# Motor-Driver-Breakout.net
KiCad netlist of a schematic drawn in EAGLE
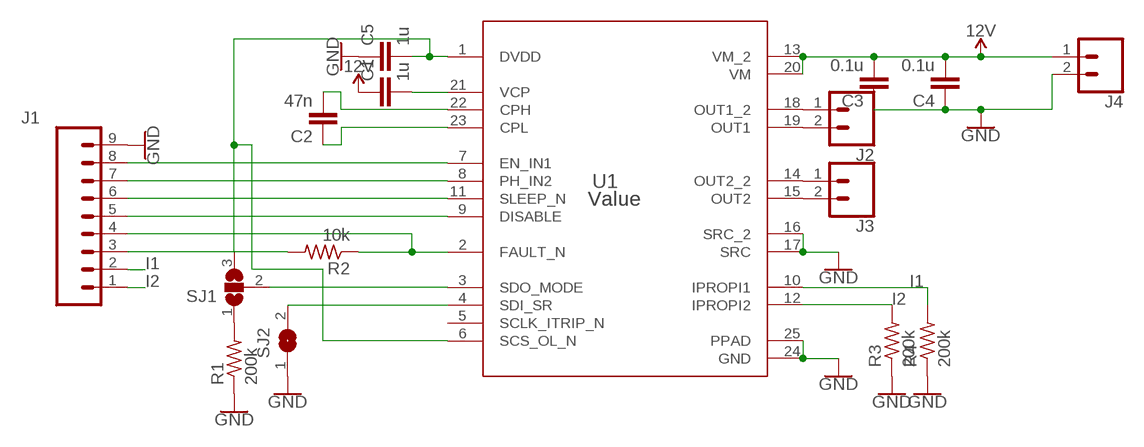
[diagram p0: schematic, sheet 1]

(export (version "E")
  (design (tool "Eeschema 10.0.6"))
  (components
    (comp (ref "C1")
      (value "1u")
      (footprint "eagle-import:0603-C")
      (libsource (lib "eagle-import") (part "C0603"))
    )
    (comp (ref "C2")
      (value "47n")
      (footprint "eagle-import:0603-C")
      (libsource (lib "eagle-import") (part "C0603"))
    )
    (comp (ref "C3")
      (value "0.1u")
      (footprint "eagle-import:0603-C")
      (libsource (lib "eagle-import") (part "C0603"))
    )
    (comp (ref "C4")
      (value "0.1u")
      (footprint "eagle-import:0603-C")
      (libsource (lib "eagle-import") (part "C0603"))
    )
    (comp (ref "C5")
      (value "1u")
      (footprint "eagle-import:0603-C")
      (libsource (lib "eagle-import") (part "C0603"))
    )
    (comp (ref "J1")
      (value "CONN_09")
      (footprint "eagle-import:1X09")
      (libsource (lib "eagle-import") (part "CONN_09"))
    )
    (comp (ref "J2")
      (value "CONN_02")
      (footprint "eagle-import:1X02")
      (libsource (lib "eagle-import") (part "CONN_02"))
    )
    (comp (ref "J3")
      (value "CONN_02")
      (footprint "eagle-import:1X02")
      (libsource (lib "eagle-import") (part "CONN_02"))
    )
    (comp (ref "J4")
      (value "CONN_02")
      (footprint "eagle-import:1X02")
      (libsource (lib "eagle-import") (part "CONN_02"))
    )
    (comp (ref "R1")
      (value "200k")
      (footprint "eagle-import:0603-R")
      (libsource (lib "eagle-import") (part "R0603"))
    )
    (comp (ref "R2")
      (value "10k")
      (footprint "eagle-import:0603-R")
      (libsource (lib "eagle-import") (part "R0603"))
    )
    (comp (ref "R3")
      (value "200k")
      (footprint "eagle-import:0603-R")
      (libsource (lib "eagle-import") (part "R0603"))
    )
    (comp (ref "R4")
      (value "200k")
      (footprint "eagle-import:0603-R")
      (libsource (lib "eagle-import") (part "R0603"))
    )
    (comp (ref "SJ1")
      (value "SJ2W")
      (footprint "eagle-import:SJ_2")
      (libsource (lib "eagle-import") (part "SJ2W"))
    )
    (comp (ref "SJ2") (value "SJ") (footprint "eagle-import:SJ") (libsource (lib "eagle-import") (part "SJ")))
    (comp (ref "U1")
      (value "Value")
      (footprint "eagle-import:PWP0024J_N")
      (fields (field (name "MANUFACTURER") "Texas Instruments") (field (name "PARTNUMBER") "DRV8873SPWPRQ1"))
      (libsource (lib "eagle-import") (part "DRV8873HPWPRQ1"))
    )
  )
  (nets
    (net (code "1") (name "/I1") (class "Default")
      (node (ref "J1") (pin "2") (pinfunction "2_2") (pintype "passive"))
      (node (ref "R4") (pin "2") (pinfunction "2_2") (pintype "passive"))
      (node (ref "U1") (pin "10") (pinfunction "IPROPI1_10") (pintype "passive"))
    )
    (net (code "2") (name "/I2") (class "Default")
      (node (ref "J1") (pin "1") (pinfunction "1_1") (pintype "passive"))
      (node (ref "R3") (pin "2") (pinfunction "2_2") (pintype "passive"))
      (node (ref "U1") (pin "12") (pinfunction "IPROPI2_12") (pintype "passive"))
    )
    (net (code "3") (name "12V") (class "Default")
      (node (ref "C1") (pin "1") (pinfunction "1_1") (pintype "passive"))
      (node (ref "C3") (pin "2") (pinfunction "2_2") (pintype "passive"))
      (node (ref "C4") (pin "2") (pinfunction "2_2") (pintype "passive"))
      (node (ref "J4") (pin "1") (pinfunction "1_1") (pintype "passive"))
      (node (ref "U1") (pin "13") (pinfunction "VM_2_13") (pintype "power_in"))
      (node (ref "U1") (pin "20") (pinfunction "VM_20") (pintype "power_in"))
    )
    (net (code "4") (name "GND") (class "Default")
      (node (ref "C3") (pin "1") (pinfunction "1_1") (pintype "passive"))
      (node (ref "C4") (pin "1") (pinfunction "1_1") (pintype "passive"))
      (node (ref "C5") (pin "1") (pinfunction "1_1") (pintype "passive"))
      (node (ref "J1") (pin "9") (pinfunction "9_9") (pintype "passive"))
      (node (ref "J4") (pin "2") (pinfunction "2_2") (pintype "passive"))
      (node (ref "R1") (pin "1") (pinfunction "1_1") (pintype "passive"))
      (node (ref "R3") (pin "1") (pinfunction "1_1") (pintype "passive"))
      (node (ref "R4") (pin "1") (pinfunction "1_1") (pintype "passive"))
      (node (ref "SJ2") (pin "1") (pinfunction "1_1") (pintype "passive"))
      (node (ref "U1") (pin "16") (pinfunction "SRC_2_16") (pintype "passive"))
      (node (ref "U1") (pin "17") (pinfunction "SRC_17") (pintype "passive"))
      (node (ref "U1") (pin "24") (pinfunction "GND_24") (pintype "power_in"))
      (node (ref "U1") (pin "25") (pinfunction "PPAD_25") (pintype "power_in"))
    )
    (net (code "5") (name "Net-(J1-Pad3)") (class "Default")
      (node (ref "J1") (pin "3") (pinfunction "3_3") (pintype "passive"))
      (node (ref "R2") (pin "2") (pinfunction "2_2") (pintype "passive"))
    )
    (net (code "6") (name "Net-(R1-Pad2)") (class "Default")
      (node (ref "R1") (pin "2") (pinfunction "2_2") (pintype "passive"))
      (node (ref "SJ1") (pin "1") (pinfunction "1_1") (pintype "passive"))
    )
    (net (code "7") (name "Net-(U1-CPH)") (class "Default")
      (node (ref "C2") (pin "2") (pinfunction "2_2") (pintype "passive"))
      (node (ref "U1") (pin "22") (pinfunction "CPH_22") (pintype "power_in"))
    )
    (net (code "8") (name "Net-(U1-CPL)") (class "Default")
      (node (ref "C2") (pin "1") (pinfunction "1_1") (pintype "passive"))
      (node (ref "U1") (pin "23") (pinfunction "CPL_23") (pintype "power_in"))
    )
    (net (code "9") (name "Net-(U1-DISABLE)") (class "Default")
      (node (ref "J1") (pin "5") (pinfunction "5_5") (pintype "passive"))
      (node (ref "U1") (pin "9") (pinfunction "DISABLE_9") (pintype "input"))
    )
    (net (code "10") (name "Net-(U1-DVDD)") (class "Default")
      (node (ref "C5") (pin "2") (pinfunction "2_2") (pintype "passive"))
      (node (ref "SJ1") (pin "3") (pinfunction "3_3") (pintype "passive"))
      (node (ref "U1") (pin "1") (pinfunction "DVDD_1") (pintype "power_in"))
      (node (ref "U1") (pin "6") (pinfunction "SCS_OL_N_6") (pintype "input"))
    )
    (net (code "11") (name "Net-(U1-EN_IN1)") (class "Default")
      (node (ref "J1") (pin "8") (pinfunction "8_8") (pintype "passive"))
      (node (ref "U1") (pin "7") (pinfunction "EN_IN1_7") (pintype "input"))
    )
    (net (code "12") (name "Net-(U1-FAULT_N)") (class "Default")
      (node (ref "J1") (pin "4") (pinfunction "4_4") (pintype "passive"))
      (node (ref "R2") (pin "1") (pinfunction "1_1") (pintype "passive"))
      (node (ref "U1") (pin "2") (pinfunction "FAULT_N_2") (pintype "open_collector"))
    )
    (net (code "13") (name "Net-(U1-OUT1)") (class "Default")
      (node (ref "J2") (pin "2") (pinfunction "2_2") (pintype "passive"))
      (node (ref "U1") (pin "19") (pinfunction "OUT1_19") (pintype "output"))
    )
    (net (code "14") (name "Net-(U1-OUT1_2)") (class "Default")
      (node (ref "J2") (pin "1") (pinfunction "1_1") (pintype "passive"))
      (node (ref "U1") (pin "18") (pinfunction "OUT1_2_18") (pintype "output"))
    )
    (net (code "15") (name "Net-(U1-OUT2)") (class "Default")
      (node (ref "J3") (pin "2") (pinfunction "2_2") (pintype "passive"))
      (node (ref "U1") (pin "15") (pinfunction "OUT2_15") (pintype "output"))
    )
    (net (code "16") (name "Net-(U1-OUT2_2)") (class "Default")
      (node (ref "J3") (pin "1") (pinfunction "1_1") (pintype "passive"))
      (node (ref "U1") (pin "14") (pinfunction "OUT2_2_14") (pintype "output"))
    )
    (net (code "17") (name "Net-(U1-PH_IN2)") (class "Default")
      (node (ref "J1") (pin "7") (pinfunction "7_7") (pintype "passive"))
      (node (ref "U1") (pin "8") (pinfunction "PH_IN2_8") (pintype "input"))
    )
    (net (code "18") (name "Net-(U1-SDI_SR)") (class "Default")
      (node (ref "SJ2") (pin "2") (pinfunction "2_2") (pintype "passive"))
      (node (ref "U1") (pin "4") (pinfunction "SDI_SR_4") (pintype "input"))
    )
    (net (code "19") (name "Net-(U1-SDO_MODE)") (class "Default")
      (node (ref "SJ1") (pin "2") (pinfunction "2_2") (pintype "passive"))
      (node (ref "U1") (pin "3") (pinfunction "SDO_MODE_3") (pintype "output"))
    )
    (net (code "20") (name "Net-(U1-SLEEP_N)") (class "Default")
      (node (ref "J1") (pin "6") (pinfunction "6_6") (pintype "passive"))
      (node (ref "U1") (pin "11") (pinfunction "SLEEP_N_11") (pintype "input"))
    )
    (net (code "21") (name "Net-(U1-VCP)") (class "Default")
      (node (ref "C1") (pin "2") (pinfunction "2_2") (pintype "passive"))
      (node (ref "U1") (pin "21") (pinfunction "VCP_21") (pintype "power_in"))
    )
    (net (code "22") (name "unconnected-(U1-SCLK_ITRIP_N-Pad5)") (class "Default")
      (node (ref "U1") (pin "5") (pinfunction "SCLK_ITRIP_N_5") (pintype "input"))
    )
  )
)
